# schematics.net
KiCad netlist of a schematic drawn in Altium Designer
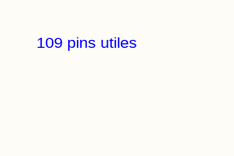
[diagram p0: schematics.schdoc, top left]
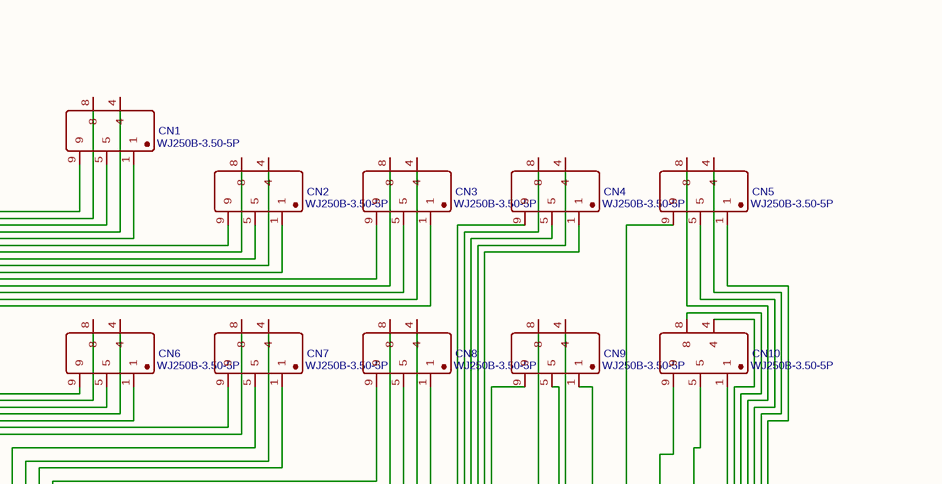
[diagram p1: schematics.schdoc, top right]
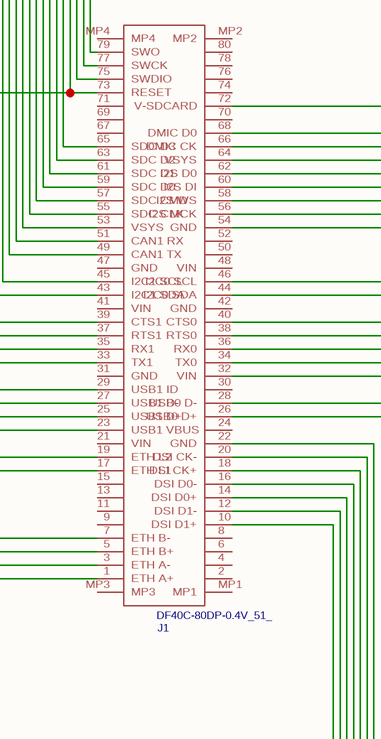
[diagram p2: schematics.schdoc, bottom left]
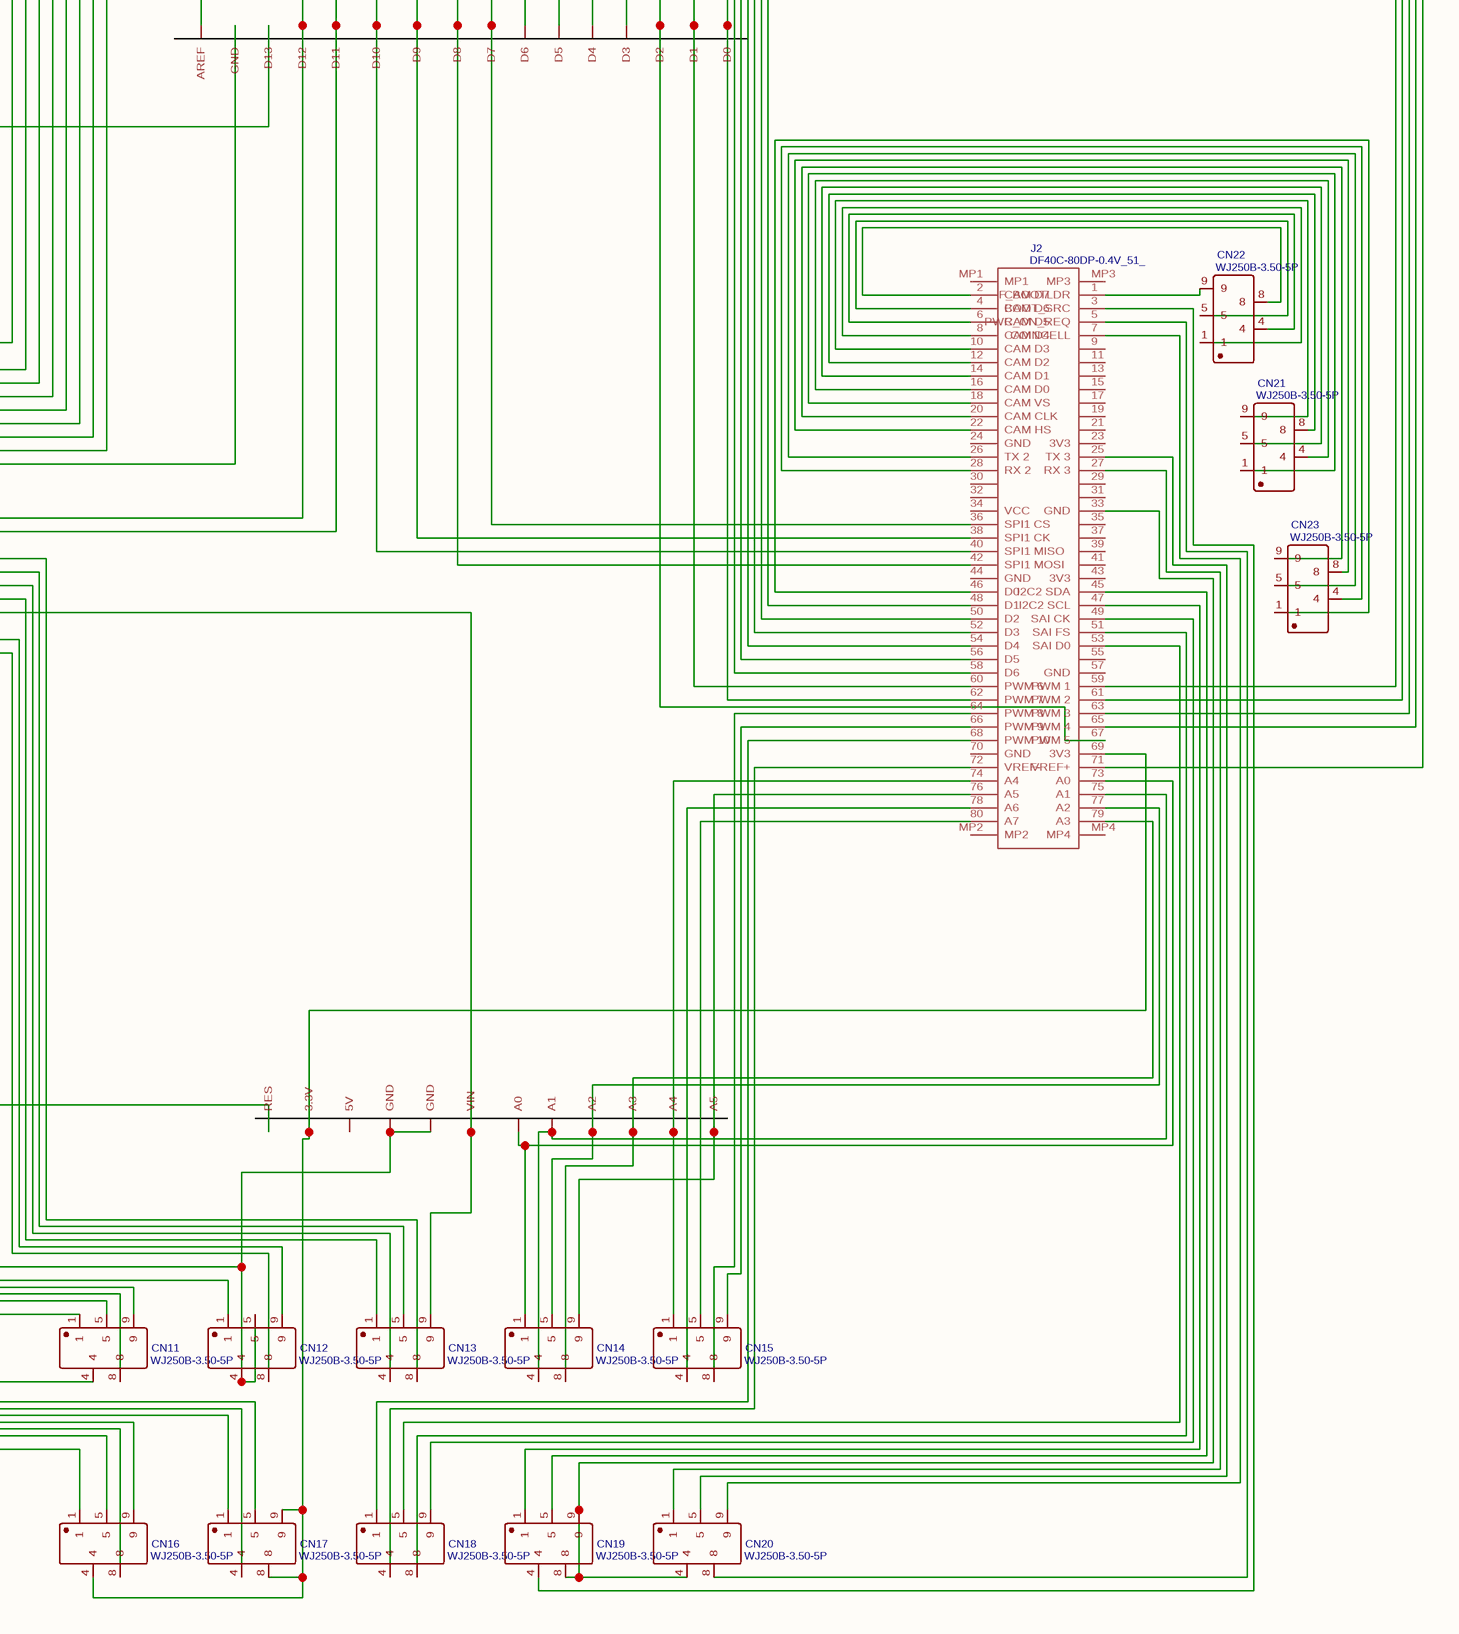
[diagram p3: schematics.schdoc, bottom right]

(export (version "E")
  (design (tool "Eeschema 10.0.6"))
  (components
    (comp (ref "CN1")
      (value "WJ250B-3.50-5P")
      (fields (field (name "BOM_SUPPLIER PART") "C8453"))
      (libsource (lib "altium-import") (part "root_3_WJ250B-3.50-5P_"))
    )
    (comp (ref "CN2")
      (value "WJ250B-3.50-5P")
      (fields (field (name "BOM_SUPPLIER PART") "C8453"))
      (libsource (lib "altium-import") (part "root_3_WJ250B-3.50-5P_"))
    )
    (comp (ref "CN3")
      (value "WJ250B-3.50-5P")
      (fields (field (name "BOM_SUPPLIER PART") "C8453"))
      (libsource (lib "altium-import") (part "root_3_WJ250B-3.50-5P_"))
    )
    (comp (ref "CN4")
      (value "WJ250B-3.50-5P")
      (fields (field (name "BOM_SUPPLIER PART") "C8453"))
      (libsource (lib "altium-import") (part "root_3_WJ250B-3.50-5P_"))
    )
    (comp (ref "CN5")
      (value "WJ250B-3.50-5P")
      (fields (field (name "BOM_SUPPLIER PART") "C8453"))
      (libsource (lib "altium-import") (part "root_3_WJ250B-3.50-5P_"))
    )
    (comp (ref "CN6")
      (value "WJ250B-3.50-5P")
      (fields (field (name "BOM_SUPPLIER PART") "C8453"))
      (libsource (lib "altium-import") (part "root_3_WJ250B-3.50-5P_"))
    )
    (comp (ref "CN7")
      (value "WJ250B-3.50-5P")
      (fields (field (name "BOM_SUPPLIER PART") "C8453"))
      (libsource (lib "altium-import") (part "root_3_WJ250B-3.50-5P_"))
    )
    (comp (ref "CN8")
      (value "WJ250B-3.50-5P")
      (fields (field (name "BOM_SUPPLIER PART") "C8453"))
      (libsource (lib "altium-import") (part "root_3_WJ250B-3.50-5P_"))
    )
    (comp (ref "CN9")
      (value "WJ250B-3.50-5P")
      (fields (field (name "BOM_SUPPLIER PART") "C8453"))
      (libsource (lib "altium-import") (part "root_3_WJ250B-3.50-5P_"))
    )
    (comp (ref "CN10")
      (value "WJ250B-3.50-5P")
      (fields (field (name "BOM_SUPPLIER PART") "C8453"))
      (libsource (lib "altium-import") (part "root_3_WJ250B-3.50-5P_"))
    )
    (comp (ref "CN11")
      (value "WJ250B-3.50-5P")
      (fields (field (name "BOM_SUPPLIER PART") "C8453"))
      (libsource (lib "altium-import") (part "root_1_WJ250B-3.50-5P_"))
    )
    (comp (ref "CN12")
      (value "WJ250B-3.50-5P")
      (fields (field (name "BOM_SUPPLIER PART") "C8453"))
      (libsource (lib "altium-import") (part "root_1_WJ250B-3.50-5P_"))
    )
    (comp (ref "CN13")
      (value "WJ250B-3.50-5P")
      (fields (field (name "BOM_SUPPLIER PART") "C8453"))
      (libsource (lib "altium-import") (part "root_1_WJ250B-3.50-5P_"))
    )
    (comp (ref "CN14")
      (value "WJ250B-3.50-5P")
      (fields (field (name "BOM_SUPPLIER PART") "C8453"))
      (libsource (lib "altium-import") (part "root_1_WJ250B-3.50-5P_"))
    )
    (comp (ref "CN15")
      (value "WJ250B-3.50-5P")
      (fields (field (name "BOM_SUPPLIER PART") "C8453"))
      (libsource (lib "altium-import") (part "root_1_WJ250B-3.50-5P_"))
    )
    (comp (ref "CN16")
      (value "WJ250B-3.50-5P")
      (fields (field (name "BOM_SUPPLIER PART") "C8453"))
      (libsource (lib "altium-import") (part "root_1_WJ250B-3.50-5P_"))
    )
    (comp (ref "CN17")
      (value "WJ250B-3.50-5P")
      (fields (field (name "BOM_SUPPLIER PART") "C8453"))
      (libsource (lib "altium-import") (part "root_1_WJ250B-3.50-5P_"))
    )
    (comp (ref "CN18")
      (value "WJ250B-3.50-5P")
      (fields (field (name "BOM_SUPPLIER PART") "C8453"))
      (libsource (lib "altium-import") (part "root_1_WJ250B-3.50-5P_"))
    )
    (comp (ref "CN19")
      (value "WJ250B-3.50-5P")
      (fields (field (name "BOM_SUPPLIER PART") "C8453"))
      (libsource (lib "altium-import") (part "root_1_WJ250B-3.50-5P_"))
    )
    (comp (ref "CN20")
      (value "WJ250B-3.50-5P")
      (fields (field (name "BOM_SUPPLIER PART") "C8453"))
      (libsource (lib "altium-import") (part "root_1_WJ250B-3.50-5P_"))
    )
    (comp (ref "CN21")
      (value "WJ250B-3.50-5P")
      (fields (field (name "BOM_SUPPLIER PART") "C8453"))
      (libsource (lib "altium-import") (part "root_2_WJ250B-3.50-5P_"))
    )
    (comp (ref "CN22")
      (value "WJ250B-3.50-5P")
      (fields (field (name "BOM_SUPPLIER PART") "C8453"))
      (libsource (lib "altium-import") (part "root_2_WJ250B-3.50-5P_"))
    )
    (comp (ref "CN23")
      (value "WJ250B-3.50-5P")
      (fields (field (name "BOM_SUPPLIER PART") "C8453"))
      (libsource (lib "altium-import") (part "root_2_WJ250B-3.50-5P_"))
    )
    (comp (ref "J1")
      (value "DF40C-80DP-0.4V_51_")
      (libsource (lib "altium-import") (part "root_0_DF40C-80DP-0.4V_51__"))
    )
    (comp (ref "J2")
      (value "DF40C-80DP-0.4V_51_")
      (libsource (lib "altium-import") (part "root_2_DF40C-80DP-0.4V_51__"))
    )
    (comp (ref "U1")
      (value "ARDUINO_SHIELDNO_SILK BIG")
      (description "Arduino shield footprint")
      (fields (field (name "CONTRIBUTOR") "SparkFun"))
      (libsource (lib "altium-import") (part "root_0_ARDUINO_SHIELDNO_SILK BIG_"))
    )
  )
  (nets
    (net (code "1") (name "Net-(CN3-Pad8)") (class "Default")
      (node (ref "CN3") (pin "8") (pinfunction "8_8") (pintype "passive"))
      (node (ref "J1") (pin "53") (pinfunction "VSYS_53") (pintype "passive"))
    )
    (net (code "2") (name "Net-(CN8-Pad9)") (class "Default")
      (node (ref "CN8") (pin "9") (pinfunction "9_9") (pintype "passive"))
      (node (ref "J1") (pin "64") (pinfunction "VSYS_64") (pintype "passive"))
    )
    (net (code "3") (name "Net-(CN12-Pad4)") (class "Default")
      (node (ref "CN12") (pin "4") (pinfunction "4_4") (pintype "passive"))
      (node (ref "CN12") (pin "5") (pinfunction "5_5") (pintype "passive"))
      (node (ref "J1") (pin "22") (pinfunction "GND_22") (pintype "passive"))
      (node (ref "U1") (pin "GND@0") (pinfunction "GND_GND@0") (pintype "passive"))
      (node (ref "U1") (pin "GND@1") (pinfunction "GND_GND@1") (pintype "passive"))
    )
    (net (code "4") (name "Net-(CN13-Pad9)") (class "Default")
      (node (ref "CN13") (pin "9") (pinfunction "9_9") (pintype "passive"))
      (node (ref "J1") (pin "32") (pinfunction "VIN_32") (pintype "passive"))
      (node (ref "U1") (pin "VIN") (pinfunction "VIN_VIN") (pintype "passive"))
    )
    (net (code "5") (name "Net-(CN16-Pad4)") (class "Default")
      (node (ref "CN16") (pin "4") (pinfunction "4_4") (pintype "passive"))
      (node (ref "CN17") (pin "8") (pinfunction "8_8") (pintype "passive"))
      (node (ref "CN17") (pin "9") (pinfunction "9_9") (pintype "passive"))
      (node (ref "J2") (pin "69") (pinfunction "3V3_69") (pintype "passive"))
      (node (ref "U1") (pin "3.3V") (pinfunction "3.3V_3.3V") (pintype "passive"))
    )
    (net (code "6") (name "Net-(CN19-Pad8)") (class "Default")
      (node (ref "CN19") (pin "8") (pinfunction "8_8") (pintype "passive"))
      (node (ref "CN19") (pin "9") (pinfunction "9_9") (pintype "passive"))
      (node (ref "CN20") (pin "4") (pinfunction "4_4") (pintype "passive"))
      (node (ref "J2") (pin "33") (pinfunction "GND_33") (pintype "passive"))
    )
    (net (code "7") (name "Net-(J1-CAN1_RX)") (class "Default")
      (node (ref "CN3") (pin "9") (pinfunction "9_9") (pintype "passive"))
      (node (ref "J1") (pin "51") (pinfunction "CAN1_RX_51") (pintype "passive"))
    )
    (net (code "8") (name "Net-(J1-CAN1_TX)") (class "Default")
      (node (ref "CN2") (pin "1") (pinfunction "1_1") (pintype "passive"))
      (node (ref "J1") (pin "49") (pinfunction "CAN1_TX_49") (pintype "passive"))
    )
    (net (code "9") (name "Net-(J1-CTS0)") (class "Default")
      (node (ref "CN13") (pin "8") (pinfunction "8_8") (pintype "passive"))
      (node (ref "J1") (pin "40") (pinfunction "CTS0_40") (pintype "passive"))
    )
    (net (code "10") (name "Net-(J1-CTS1)") (class "Default")
      (node (ref "CN2") (pin "8") (pinfunction "8_8") (pintype "passive"))
      (node (ref "J1") (pin "39") (pinfunction "CTS1_39") (pintype "passive"))
    )
    (net (code "11") (name "Net-(J1-DMIC_CK)") (class "Default")
      (node (ref "CN7") (pin "1") (pinfunction "1_1") (pintype "passive"))
      (node (ref "J1") (pin "66") (pinfunction "DMIC_CK_66") (pintype "passive"))
    )
    (net (code "12") (name "Net-(J1-DMIC_D0)") (class "Default")
      (node (ref "CN7") (pin "4") (pinfunction "4_4") (pintype "passive"))
      (node (ref "J1") (pin "68") (pinfunction "DMIC_D0_68") (pintype "passive"))
    )
    (net (code "13") (name "Net-(J1-DSI_CK+)") (class "Default")
      (node (ref "CN11") (pin "9") (pinfunction "9_9") (pintype "passive"))
      (node (ref "J1") (pin "18") (pinfunction "DSI_CK+_18") (pintype "passive"))
    )
    (net (code "14") (name "Net-(J1-DSI_CK-)") (class "Default")
      (node (ref "CN12") (pin "1") (pinfunction "1_1") (pintype "passive"))
      (node (ref "J1") (pin "20") (pinfunction "DSI_CK-_20") (pintype "passive"))
    )
    (net (code "15") (name "Net-(J1-DSI_D0+)") (class "Default")
      (node (ref "CN11") (pin "5") (pinfunction "5_5") (pintype "passive"))
      (node (ref "J1") (pin "14") (pinfunction "DSI_D0+_14") (pintype "passive"))
    )
    (net (code "16") (name "Net-(J1-DSI_D0-)") (class "Default")
      (node (ref "CN11") (pin "8") (pinfunction "8_8") (pintype "passive"))
      (node (ref "J1") (pin "16") (pinfunction "DSI_D0-_16") (pintype "passive"))
    )
    (net (code "17") (name "Net-(J1-DSI_D1+)") (class "Default")
      (node (ref "CN11") (pin "4") (pinfunction "4_4") (pintype "passive"))
      (node (ref "J1") (pin "10") (pinfunction "DSI_D1+_10") (pintype "passive"))
    )
    (net (code "18") (name "Net-(J1-DSI_D1-)") (class "Default")
      (node (ref "CN11") (pin "1") (pinfunction "1_1") (pintype "passive"))
      (node (ref "J1") (pin "12") (pinfunction "DSI_D1-_12") (pintype "passive"))
    )
    (net (code "19") (name "Net-(J1-ETH_A+)") (class "Default")
      (node (ref "CN17") (pin "5") (pinfunction "5_5") (pintype "passive"))
      (node (ref "J1") (pin "1") (pinfunction "ETH_A+_1") (pintype "passive"))
    )
    (net (code "20") (name "Net-(J1-ETH_A-)") (class "Default")
      (node (ref "CN17") (pin "4") (pinfunction "4_4") (pintype "passive"))
      (node (ref "J1") (pin "3") (pinfunction "ETH_A-_3") (pintype "passive"))
    )
    (net (code "21") (name "Net-(J1-ETH_B+)") (class "Default")
      (node (ref "CN17") (pin "1") (pinfunction "1_1") (pintype "passive"))
      (node (ref "J1") (pin "5") (pinfunction "ETH_B+_5") (pintype "passive"))
    )
    (net (code "22") (name "Net-(J1-ETH_B-)") (class "Default")
      (node (ref "CN16") (pin "9") (pinfunction "9_9") (pintype "passive"))
      (node (ref "J1") (pin "7") (pinfunction "ETH_B-_7") (pintype "passive"))
    )
    (net (code "23") (name "Net-(J1-ETH_L1)") (class "Default")
      (node (ref "CN16") (pin "8") (pinfunction "8_8") (pintype "passive"))
      (node (ref "J1") (pin "17") (pinfunction "ETH_L1_17") (pintype "passive"))
    )
    (net (code "24") (name "Net-(J1-ETH_L2)") (class "Default")
      (node (ref "CN16") (pin "5") (pinfunction "5_5") (pintype "passive"))
      (node (ref "J1") (pin "19") (pinfunction "ETH_L2_19") (pintype "passive"))
    )
    (net (code "25") (name "Net-(J1-GND-Pad54)") (class "Default")
      (node (ref "J1") (pin "54") (pinfunction "GND_54") (pintype "passive"))
      (node (ref "U1") (pin "GND@2") (pinfunction "GND_GND@2") (pintype "passive"))
    )
    (net (code "26") (name "Net-(J1-I2C0_SCL)") (class "Default")
      (node (ref "CN4") (pin "9") (pinfunction "9_9") (pintype "passive"))
      (node (ref "J1") (pin "46") (pinfunction "I2C0_SCL_46") (pintype "passive"))
      (node (ref "U1") (pin "D12") (pinfunction "D12_D12") (pintype "passive"))
    )
    (net (code "27") (name "Net-(J1-I2C0_SDA)") (class "Default")
      (node (ref "CN4") (pin "8") (pinfunction "8_8") (pintype "passive"))
      (node (ref "J1") (pin "44") (pinfunction "I2C0_SDA_44") (pintype "passive"))
      (node (ref "U1") (pin "D11") (pinfunction "D11_D11") (pintype "passive"))
    )
    (net (code "28") (name "Net-(J1-I2C1_SCL)") (class "Default")
      (node (ref "CN2") (pin "4") (pinfunction "4_4") (pintype "passive"))
      (node (ref "J1") (pin "45") (pinfunction "I2C1_SCL_45") (pintype "passive"))
    )
    (net (code "29") (name "Net-(J1-I2C1_SDA)") (class "Default")
      (node (ref "CN2") (pin "5") (pinfunction "5_5") (pintype "passive"))
      (node (ref "J1") (pin "43") (pinfunction "I2C1_SDA_43") (pintype "passive"))
    )
    (net (code "30") (name "Net-(J1-I2S_D0)") (class "Default")
      (node (ref "CN8") (pin "8") (pinfunction "8_8") (pintype "passive"))
      (node (ref "J1") (pin "62") (pinfunction "I2S_D0_62") (pintype "passive"))
    )
    (net (code "31") (name "Net-(J1-I2S_DI)") (class "Default")
      (node (ref "CN8") (pin "5") (pinfunction "5_5") (pintype "passive"))
      (node (ref "J1") (pin "60") (pinfunction "I2S_DI_60") (pintype "passive"))
    )
    (net (code "32") (name "Net-(J1-I2S_MCK)") (class "Default")
      (node (ref "CN8") (pin "1") (pinfunction "1_1") (pintype "passive"))
      (node (ref "J1") (pin "56") (pinfunction "I2S_MCK_56") (pintype "passive"))
    )
    (net (code "33") (name "Net-(J1-I2S_WS)") (class "Default")
      (node (ref "CN8") (pin "4") (pinfunction "4_4") (pintype "passive"))
      (node (ref "J1") (pin "58") (pinfunction "I2S_WS_58") (pintype "passive"))
    )
    (net (code "34") (name "Net-(J1-RESET)") (class "Default")
      (node (ref "CN6") (pin "4") (pinfunction "4_4") (pintype "passive"))
      (node (ref "J1") (pin "73") (pinfunction "RESET_73") (pintype "passive"))
      (node (ref "U1") (pin "RES") (pinfunction "RES_RES") (pintype "passive"))
    )
    (net (code "35") (name "Net-(J1-RTS0)") (class "Default")
      (node (ref "CN13") (pin "5") (pinfunction "5_5") (pintype "passive"))
      (node (ref "J1") (pin "38") (pinfunction "RTS0_38") (pintype "passive"))
    )
    (net (code "36") (name "Net-(J1-RTS1)") (class "Default")
      (node (ref "CN2") (pin "9") (pinfunction "9_9") (pintype "passive"))
      (node (ref "J1") (pin "37") (pinfunction "RTS1_37") (pintype "passive"))
    )
    (net (code "37") (name "Net-(J1-RX0)") (class "Default")
      (node (ref "CN13") (pin "4") (pinfunction "4_4") (pintype "passive"))
      (node (ref "J1") (pin "36") (pinfunction "RX0_36") (pintype "passive"))
    )
    (net (code "38") (name "Net-(J1-RX1)") (class "Default")
      (node (ref "CN1") (pin "1") (pinfunction "1_1") (pintype "passive"))
      (node (ref "J1") (pin "35") (pinfunction "RX1_35") (pintype "passive"))
      (node (ref "U1") (pin "D13") (pinfunction "D13_D13") (pintype "passive"))
    )
    (net (code "39") (name "Net-(J1-SDC_CLK)") (class "Default")
      (node (ref "CN3") (pin "5") (pinfunction "5_5") (pintype "passive"))
      (node (ref "J1") (pin "55") (pinfunction "SDC_CLK_55") (pintype "passive"))
    )
    (net (code "40") (name "Net-(J1-SDC_CMD)") (class "Default")
      (node (ref "CN3") (pin "4") (pinfunction "4_4") (pintype "passive"))
      (node (ref "J1") (pin "57") (pinfunction "SDC_CMD_57") (pintype "passive"))
    )
    (net (code "41") (name "Net-(J1-SDC_D0)") (class "Default")
      (node (ref "CN3") (pin "1") (pinfunction "1_1") (pintype "passive"))
      (node (ref "J1") (pin "59") (pinfunction "SDC_D0_59") (pintype "passive"))
    )
    (net (code "42") (name "Net-(J1-SDC_D1)") (class "Default")
      (node (ref "CN6") (pin "9") (pinfunction "9_9") (pintype "passive"))
      (node (ref "J1") (pin "61") (pinfunction "SDC_D1_61") (pintype "passive"))
    )
    (net (code "43") (name "Net-(J1-SDC_D2)") (class "Default")
      (node (ref "CN6") (pin "8") (pinfunction "8_8") (pintype "passive"))
      (node (ref "J1") (pin "63") (pinfunction "SDC_D2_63") (pintype "passive"))
    )
    (net (code "44") (name "Net-(J1-SDC_D3)") (class "Default")
      (node (ref "CN6") (pin "5") (pinfunction "5_5") (pintype "passive"))
      (node (ref "J1") (pin "65") (pinfunction "SDC_D3_65") (pintype "passive"))
    )
    (net (code "45") (name "Net-(J1-SWCK)") (class "Default")
      (node (ref "CN7") (pin "9") (pinfunction "9_9") (pintype "passive"))
      (node (ref "J1") (pin "77") (pinfunction "SWCK_77") (pintype "passive"))
    )
    (net (code "46") (name "Net-(J1-SWDIO)") (class "Default")
      (node (ref "CN6") (pin "1") (pinfunction "1_1") (pintype "passive"))
      (node (ref "J1") (pin "75") (pinfunction "SWDIO_75") (pintype "passive"))
    )
    (net (code "47") (name "Net-(J1-SWO)") (class "Default")
      (node (ref "CN7") (pin "8") (pinfunction "8_8") (pintype "passive"))
      (node (ref "J1") (pin "79") (pinfunction "SWO_79") (pintype "passive"))
    )
    (net (code "48") (name "Net-(J1-TX0)") (class "Default")
      (node (ref "CN13") (pin "1") (pinfunction "1_1") (pintype "passive"))
      (node (ref "J1") (pin "34") (pinfunction "TX0_34") (pintype "passive"))
    )
    (net (code "49") (name "Net-(J1-TX1)") (class "Default")
      (node (ref "CN1") (pin "4") (pinfunction "4_4") (pintype "passive"))
      (node (ref "J1") (pin "33") (pinfunction "TX1_33") (pintype "passive"))
    )
    (net (code "50") (name "Net-(J1-USB0_D+)") (class "Default")
      (node (ref "CN12") (pin "8") (pinfunction "8_8") (pintype "passive"))
      (node (ref "J1") (pin "26") (pinfunction "USB0_D+_26") (pintype "passive"))
    )
    (net (code "51") (name "Net-(J1-USB0_D-)") (class "Default")
      (node (ref "CN12") (pin "9") (pinfunction "9_9") (pintype "passive"))
      (node (ref "J1") (pin "28") (pinfunction "USB0_D-_28") (pintype "passive"))
    )
    (net (code "52") (name "Net-(J1-USB1_D+)") (class "Default")
      (node (ref "CN1") (pin "9") (pinfunction "9_9") (pintype "passive"))
      (node (ref "J1") (pin "25") (pinfunction "USB1_D+_25") (pintype "passive"))
    )
    (net (code "53") (name "Net-(J1-USB1_D-)") (class "Default")
      (node (ref "CN1") (pin "8") (pinfunction "8_8") (pintype "passive"))
      (node (ref "J1") (pin "27") (pinfunction "USB1_D-_27") (pintype "passive"))
    )
    (net (code "54") (name "Net-(J1-USB1_ID)") (class "Default")
      (node (ref "CN1") (pin "5") (pinfunction "5_5") (pintype "passive"))
      (node (ref "J1") (pin "29") (pinfunction "USB1_ID_29") (pintype "passive"))
    )
    (net (code "55") (name "Net-(J1-USB1_VBUS)") (class "Default")
      (node (ref "CN16") (pin "1") (pinfunction "1_1") (pintype "passive"))
      (node (ref "J1") (pin "23") (pinfunction "USB1_VBUS_23") (pintype "passive"))
    )
    (net (code "56") (name "Net-(J1-V-SDCARD)") (class "Default")
      (node (ref "CN7") (pin "5") (pinfunction "5_5") (pintype "passive"))
      (node (ref "J1") (pin "72") (pinfunction "V-SDCARD_72") (pintype "passive"))
    )
    (net (code "57") (name "Net-(J2-A0)") (class "Default")
      (node (ref "CN14") (pin "1") (pinfunction "1_1") (pintype "passive"))
      (node (ref "J2") (pin "73") (pinfunction "A0_73") (pintype "passive"))
      (node (ref "U1") (pin "A0") (pinfunction "A0_A0") (pintype "passive"))
    )
    (net (code "58") (name "Net-(J2-A1)") (class "Default")
      (node (ref "CN14") (pin "4") (pinfunction "4_4") (pintype "passive"))
      (node (ref "J2") (pin "75") (pinfunction "A1_75") (pintype "passive"))
      (node (ref "U1") (pin "A1") (pinfunction "A1_A1") (pintype "passive"))
    )
    (net (code "59") (name "Net-(J2-A2)") (class "Default")
      (node (ref "CN14") (pin "5") (pinfunction "5_5") (pintype "passive"))
      (node (ref "J2") (pin "77") (pinfunction "A2_77") (pintype "passive"))
      (node (ref "U1") (pin "A2") (pinfunction "A2_A2") (pintype "passive"))
    )
    (net (code "60") (name "Net-(J2-A3)") (class "Default")
      (node (ref "CN14") (pin "8") (pinfunction "8_8") (pintype "passive"))
      (node (ref "J2") (pin "79") (pinfunction "A3_79") (pintype "passive"))
      (node (ref "U1") (pin "A3") (pinfunction "A3_A3") (pintype "passive"))
    )
    (net (code "61") (name "Net-(J2-A4)") (class "Default")
      (node (ref "CN14") (pin "9") (pinfunction "9_9") (pintype "passive"))
      (node (ref "CN15") (pin "1") (pinfunction "1_1") (pintype "passive"))
      (node (ref "J2") (pin "74") (pinfunction "A4_74") (pintype "passive"))
      (node (ref "J2") (pin "76") (pinfunction "A5_76") (pintype "passive"))
      (node (ref "U1") (pin "A4") (pinfunction "A4_A4") (pintype "passive"))
      (node (ref "U1") (pin "A5") (pinfunction "A5_A5") (pintype "passive"))
    )
    (net (code "62") (name "Net-(J2-A6)") (class "Default")
      (node (ref "CN15") (pin "4") (pinfunction "4_4") (pintype "passive"))
      (node (ref "J2") (pin "78") (pinfunction "A6_78") (pintype "passive"))
    )
    (net (code "63") (name "Net-(J2-A7)") (class "Default")
      (node (ref "CN15") (pin "5") (pinfunction "5_5") (pintype "passive"))
      (node (ref "J2") (pin "80") (pinfunction "A7_80") (pintype "passive"))
    )
    (net (code "64") (name "Net-(J2-BOOT_SRC)") (class "Default")
      (node (ref "CN19") (pin "4") (pinfunction "4_4") (pintype "passive"))
      (node (ref "J2") (pin "3") (pinfunction "BOOT_SRC_3") (pintype "passive"))
    )
    (net (code "65") (name "Net-(J2-CAM_CLK)") (class "Default")
      (node (ref "CN23") (pin "9") (pinfunction "9_9") (pintype "passive"))
      (node (ref "J2") (pin "20") (pinfunction "CAM_CLK_20") (pintype "passive"))
    )
    (net (code "66") (name "Net-(J2-CAM_D0)") (class "Default")
      (node (ref "CN21") (pin "4") (pinfunction "4_4") (pintype "passive"))
      (node (ref "J2") (pin "16") (pinfunction "CAM_D0_16") (pintype "passive"))
    )
    (net (code "67") (name "Net-(J2-CAM_D1)") (class "Default")
      (node (ref "CN21") (pin "5") (pinfunction "5_5") (pintype "passive"))
      (node (ref "J2") (pin "14") (pinfunction "CAM_D1_14") (pintype "passive"))
    )
    (net (code "68") (name "Net-(J2-CAM_D2)") (class "Default")
      (node (ref "CN21") (pin "8") (pinfunction "8_8") (pintype "passive"))
      (node (ref "J2") (pin "12") (pinfunction "CAM_D2_12") (pintype "passive"))
    )
    (net (code "69") (name "Net-(J2-CAM_D3)") (class "Default")
      (node (ref "CN21") (pin "9") (pinfunction "9_9") (pintype "passive"))
      (node (ref "J2") (pin "10") (pinfunction "CAM_D3_10") (pintype "passive"))
    )
    (net (code "70") (name "Net-(J2-CAM_D4)") (class "Default")
      (node (ref "CN22") (pin "1") (pinfunction "1_1") (pintype "passive"))
      (node (ref "J2") (pin "8") (pinfunction "CAM_D4_8") (pintype "passive"))
    )
    (net (code "71") (name "Net-(J2-CAM_D5)") (class "Default")
      (node (ref "CN22") (pin "4") (pinfunction "4_4") (pintype "passive"))
      (node (ref "J2") (pin "6") (pinfunction "CAM_D5_6") (pintype "passive"))
    )
    (net (code "72") (name "Net-(J2-CAM_D6)") (class "Default")
      (node (ref "CN22") (pin "5") (pinfunction "5_5") (pintype "passive"))
      (node (ref "J2") (pin "4") (pinfunction "CAM_D6_4") (pintype "passive"))
    )
    (net (code "73") (name "Net-(J2-CAM_D7)") (class "Default")
      (node (ref "CN22") (pin "8") (pinfunction "8_8") (pintype "passive"))
      (node (ref "J2") (pin "2") (pinfunction "CAM_D7_2") (pintype "passive"))
    )
    (net (code "74") (name "Net-(J2-CAM_HS)") (class "Default")
      (node (ref "CN23") (pin "8") (pinfunction "8_8") (pintype "passive"))
      (node (ref "J2") (pin "22") (pinfunction "CAM_HS_22") (pintype "passive"))
    )
    (net (code "75") (name "Net-(J2-CAM_VS)") (class "Default")
      (node (ref "CN21") (pin "1") (pinfunction "1_1") (pintype "passive"))
      (node (ref "J2") (pin "18") (pinfunction "CAM_VS_18") (pintype "passive"))
    )
    (net (code "76") (name "Net-(J2-COINCELL)") (class "Default")
      (node (ref "CN20") (pin "9") (pinfunction "9_9") (pintype "passive"))
      (node (ref "J2") (pin "7") (pinfunction "COINCELL_7") (pintype "passive"))
    )
    (net (code "77") (name "Net-(J2-D0)") (class "Default")
      (node (ref "CN23") (pin "1") (pinfunction "1_1") (pintype "passive"))
      (node (ref "J2") (pin "46") (pinfunction "D0_46") (pintype "passive"))
    )
    (net (code "78") (name "Net-(J2-D1)") (class "Default")
      (node (ref "CN5") (pin "1") (pinfunction "1_1") (pintype "passive"))
      (node (ref "J2") (pin "48") (pinfunction "D1_48") (pintype "passive"))
    )
    (net (code "79") (name "Net-(J2-D2)") (class "Default")
      (node (ref "CN5") (pin "4") (pinfunction "4_4") (pintype "passive"))
      (node (ref "J2") (pin "50") (pinfunction "D2_50") (pintype "passive"))
    )
    (net (code "80") (name "Net-(J2-D3)") (class "Default")
      (node (ref "CN5") (pin "5") (pinfunction "5_5") (pintype "passive"))
      (node (ref "J2") (pin "52") (pinfunction "D3_52") (pintype "passive"))
    )
    (net (code "81") (name "Net-(J2-D4)") (class "Default")
      (node (ref "CN5") (pin "8") (pinfunction "8_8") (pintype "passive"))
      (node (ref "J2") (pin "54") (pinfunction "D4_54") (pintype "passive"))
    )
    (net (code "82") (name "Net-(J2-D5)") (class "Default")
      (node (ref "CN10") (pin "8") (pinfunction "8_8") (pintype "passive"))
      (node (ref "J2") (pin "56") (pinfunction "D5_56") (pintype "passive"))
    )
    (net (code "83") (name "Net-(J2-D6)") (class "Default")
      (node (ref "CN10") (pin "4") (pinfunction "4_4") (pintype "passive"))
      (node (ref "J2") (pin "58") (pinfunction "D6_58") (pintype "passive"))
    )
    (net (code "84") (name "Net-(J2-F_BOOTLDR)") (class "Default")
      (node (ref "CN22") (pin "9") (pinfunction "9_9") (pintype "passive"))
      (node (ref "J2") (pin "1") (pinfunction "F_BOOTLDR_1") (pintype "passive"))
    )
    (net (code "85") (name "Net-(J2-I2C2_SCL)") (class "Default")
      (node (ref "CN19") (pin "1") (pinfunction "1_1") (pintype "passive"))
      (node (ref "J2") (pin "47") (pinfunction "I2C2_SCL_47") (pintype "passive"))
    )
    (net (code "86") (name "Net-(J2-I2C2_SDA)") (class "Default")
      (node (ref "CN19") (pin "5") (pinfunction "5_5") (pintype "passive"))
      (node (ref "J2") (pin "45") (pinfunction "I2C2_SDA_45") (pintype "passive"))
    )
    (net (code "87") (name "Net-(J2-PWM_1)") (class "Default")
      (node (ref "CN9") (pin "8") (pinfunction "8_8") (pintype "passive"))
      (node (ref "J2") (pin "59") (pinfunction "PWM_1_59") (pintype "passive"))
      (node (ref "U1") (pin "D6") (pinfunction "D6_D6") (pintype "passive"))
    )
    (net (code "88") (name "Net-(J2-PWM_2)") (class "Default")
      (node (ref "CN9") (pin "5") (pinfunction "5_5") (pintype "passive"))
      (node (ref "J2") (pin "61") (pinfunction "PWM_2_61") (pintype "passive"))
      (node (ref "U1") (pin "D5") (pinfunction "D5_D5") (pintype "passive"))
    )
    (net (code "89") (name "Net-(J2-PWM_3)") (class "Default")
      (node (ref "CN9") (pin "1") (pinfunction "1_1") (pintype "passive"))
      (node (ref "J2") (pin "63") (pinfunction "PWM_3_63") (pintype "passive"))
      (node (ref "U1") (pin "D4") (pinfunction "D4_D4") (pintype "passive"))
    )
    (net (code "90") (name "Net-(J2-PWM_4)") (class "Default")
      (node (ref "CN5") (pin "9") (pinfunction "9_9") (pintype "passive"))
      (node (ref "J2") (pin "65") (pinfunction "PWM_4_65") (pintype "passive"))
      (node (ref "U1") (pin "D3") (pinfunction "D3_D3") (pintype "passive"))
    )
    (net (code "91") (name "Net-(J2-PWM_5)") (class "Default")
      (node (ref "CN10") (pin "9") (pinfunction "9_9") (pintype "passive"))
      (node (ref "J2") (pin "67") (pinfunction "PWM_5_67") (pintype "passive"))
      (node (ref "U1") (pin "D2") (pinfunction "D2_D2") (pintype "passive"))
    )
    (net (code "92") (name "Net-(J2-PWM_6)") (class "Default")
      (node (ref "CN10") (pin "5") (pinfunction "5_5") (pintype "passive"))
      (node (ref "J2") (pin "60") (pinfunction "PWM_6_60") (pintype "passive"))
      (node (ref "U1") (pin "TX") (pinfunction "D1_TX") (pintype "passive"))
    )
    (net (code "93") (name "Net-(J2-PWM_7)") (class "Default")
      (node (ref "CN10") (pin "1") (pinfunction "1_1") (pintype "passive"))
      (node (ref "J2") (pin "62") (pinfunction "PWM_7_62") (pintype "passive"))
      (node (ref "U1") (pin "RX") (pinfunction "D0_RX") (pintype "passive"))
    )
    (net (code "94") (name "Net-(J2-PWM_8)") (class "Default")
      (node (ref "CN15") (pin "8") (pinfunction "8_8") (pintype "passive"))
      (node (ref "J2") (pin "64") (pinfunction "PWM_8_64") (pintype "passive"))
    )
    (net (code "95") (name "Net-(J2-PWM_9)") (class "Default")
      (node (ref "CN15") (pin "9") (pinfunction "9_9") (pintype "passive"))
      (node (ref "J2") (pin "66") (pinfunction "PWM_9_66") (pintype "passive"))
    )
    (net (code "96") (name "Net-(J2-PWM_10)") (class "Default")
      (node (ref "CN18") (pin "1") (pinfunction "1_1") (pintype "passive"))
      (node (ref "J2") (pin "68") (pinfunction "PWM_10_68") (pintype "passive"))
    )
    (net (code "97") (name "Net-(J2-PWR_ON_REQ)") (class "Default")
      (node (ref "CN20") (pin "8") (pinfunction "8_8") (pintype "passive"))
      (node (ref "J2") (pin "5") (pinfunction "PWR_ON_REQ_5") (pintype "passive"))
    )
    (net (code "98") (name "Net-(J2-RX_2)") (class "Default")
      (node (ref "CN23") (pin "4") (pinfunction "4_4") (pintype "passive"))
      (node (ref "J2") (pin "28") (pinfunction "RX_2_28") (pintype "passive"))
    )
    (net (code "99") (name "Net-(J2-RX_3)") (class "Default")
      (node (ref "CN20") (pin "1") (pinfunction "1_1") (pintype "passive"))
      (node (ref "J2") (pin "27") (pinfunction "RX_3_27") (pintype "passive"))
    )
    (net (code "100") (name "Net-(J2-SAI_CK)") (class "Default")
      (node (ref "CN18") (pin "9") (pinfunction "9_9") (pintype "passive"))
      (node (ref "J2") (pin "49") (pinfunction "SAI_CK_49") (pintype "passive"))
    )
    (net (code "101") (name "Net-(J2-SAI_D0)") (class "Default")
      (node (ref "CN18") (pin "5") (pinfunction "5_5") (pintype "passive"))
      (node (ref "J2") (pin "53") (pinfunction "SAI_D0_53") (pintype "passive"))
    )
    (net (code "102") (name "Net-(J2-SAI_FS)") (class "Default")
      (node (ref "CN18") (pin "8") (pinfunction "8_8") (pintype "passive"))
      (node (ref "J2") (pin "51") (pinfunction "SAI_FS_51") (pintype "passive"))
    )
    (net (code "103") (name "Net-(J2-SPI1_CK)") (class "Default")
      (node (ref "CN4") (pin "4") (pinfunction "4_4") (pintype "passive"))
      (node (ref "J2") (pin "38") (pinfunction "SPI1_CK_38") (pintype "passive"))
      (node (ref "U1") (pin "D9") (pinfunction "D9_D9") (pintype "passive"))
    )
    (net (code "104") (name "Net-(J2-SPI1_CS)") (class "Default")
      (node (ref "CN9") (pin "9") (pinfunction "9_9") (pintype "passive"))
      (node (ref "J2") (pin "36") (pinfunction "SPI1_CS_36") (pintype "passive"))
      (node (ref "U1") (pin "D7") (pinfunction "D7_D7") (pintype "passive"))
    )
    (net (code "105") (name "Net-(J2-SPI1_MISO)") (class "Default")
      (node (ref "CN4") (pin "5") (pinfunction "5_5") (pintype "passive"))
      (node (ref "J2") (pin "40") (pinfunction "SPI1_MISO_40") (pintype "passive"))
      (node (ref "U1") (pin "D10") (pinfunction "D10_D10") (pintype "passive"))
    )
    (net (code "106") (name "Net-(J2-SPI1_MOSI)") (class "Default")
      (node (ref "CN4") (pin "1") (pinfunction "1_1") (pintype "passive"))
      (node (ref "J2") (pin "42") (pinfunction "SPI1_MOSI_42") (pintype "passive"))
      (node (ref "U1") (pin "D8") (pinfunction "D8_D8") (pintype "passive"))
    )
    (net (code "107") (name "Net-(J2-TX_2)") (class "Default")
      (node (ref "CN23") (pin "5") (pinfunction "5_5") (pintype "passive"))
      (node (ref "J2") (pin "26") (pinfunction "TX_2_26") (pintype "passive"))
    )
    (net (code "108") (name "Net-(J2-TX_3)") (class "Default")
      (node (ref "CN20") (pin "5") (pinfunction "5_5") (pintype "passive"))
      (node (ref "J2") (pin "25") (pinfunction "TX_3_25") (pintype "passive"))
    )
    (net (code "109") (name "Net-(J2-VREF+)") (class "Default")
      (node (ref "CN9") (pin "4") (pinfunction "4_4") (pintype "passive"))
      (node (ref "J2") (pin "71") (pinfunction "VREF+_71") (pintype "passive"))
      (node (ref "U1") (pin "AREF") (pinfunction "AREF_AREF") (pintype "passive"))
    )
    (net (code "110") (name "Net-(J2-VREF-)") (class "Default")
      (node (ref "CN18") (pin "4") (pinfunction "4_4") (pintype "passive"))
      (node (ref "J2") (pin "72") (pinfunction "VREF-_72") (pintype "passive"))
    )
    (net (code "111") (name "unconnected-(J1-GND-Pad31)") (class "Default")
      (node (ref "J1") (pin "31") (pinfunction "GND_31") (pintype "passive"))
    )
    (net (code "112") (name "unconnected-(J1-GND-Pad42)") (class "Default")
      (node (ref "J1") (pin "42") (pinfunction "GND_42") (pintype "passive"))
    )
    (net (code "113") (name "unconnected-(J1-GND-Pad47)") (class "Default")
      (node (ref "J1") (pin "47") (pinfunction "GND_47") (pintype "passive"))
    )
    (net (code "114") (name "unconnected-(J1-Pad2)") (class "Default")
      (node (ref "J1") (pin "2") (pintype "passive"))
    )
    (net (code "115") (name "unconnected-(J1-Pad4)") (class "Default")
      (node (ref "J1") (pin "4") (pintype "passive"))
    )
    (net (code "116") (name "unconnected-(J1-Pad6)") (class "Default")
      (node (ref "J1") (pin "6") (pintype "passive"))
    )
    (net (code "117") (name "unconnected-(J1-Pad8)") (class "Default")
      (node (ref "J1") (pin "8") (pintype "passive"))
    )
    (net (code "118") (name "unconnected-(J1-Pad9)") (class "Default")
      (node (ref "J1") (pin "9") (pintype "passive"))
    )
    (net (code "119") (name "unconnected-(J1-Pad11)") (class "Default")
      (node (ref "J1") (pin "11") (pintype "passive"))
    )
    (net (code "120") (name "unconnected-(J1-Pad13)") (class "Default")
      (node (ref "J1") (pin "13") (pintype "passive"))
    )
    (net (code "121") (name "unconnected-(J1-Pad15)") (class "Default")
      (node (ref "J1") (pin "15") (pintype "passive"))
    )
    (net (code "122") (name "unconnected-(J1-Pad24)") (class "Default")
      (node (ref "J1") (pin "24") (pintype "passive"))
    )
    (net (code "123") (name "unconnected-(J1-Pad30)") (class "Default")
      (node (ref "J1") (pin "30") (pintype "passive"))
    )
    (net (code "124") (name "unconnected-(J1-Pad50)") (class "Default")
      (node (ref "J1") (pin "50") (pintype "passive"))
    )
    (net (code "125") (name "unconnected-(J1-Pad52)") (class "Default")
      (node (ref "J1") (pin "52") (pintype "passive"))
    )
    (net (code "126") (name "unconnected-(J1-Pad67)") (class "Default")
      (node (ref "J1") (pin "67") (pintype "passive"))
    )
    (net (code "127") (name "unconnected-(J1-Pad69)") (class "Default")
      (node (ref "J1") (pin "69") (pintype "passive"))
    )
    (net (code "128") (name "unconnected-(J1-Pad70)") (class "Default")
      (node (ref "J1") (pin "70") (pintype "passive"))
    )
    (net (code "129") (name "unconnected-(J1-Pad71)") (class "Default")
      (node (ref "J1") (pin "71") (pintype "passive"))
    )
    (net (code "130") (name "unconnected-(J1-Pad74)") (class "Default")
      (node (ref "J1") (pin "74") (pintype "passive"))
    )
    (net (code "131") (name "unconnected-(J1-Pad76)") (class "Default")
      (node (ref "J1") (pin "76") (pintype "passive"))
    )
    (net (code "132") (name "unconnected-(J1-Pad78)") (class "Default")
      (node (ref "J1") (pin "78") (pintype "passive"))
    )
    (net (code "133") (name "unconnected-(J1-Pad80)") (class "Default")
      (node (ref "J1") (pin "80") (pintype "passive"))
    )
    (net (code "134") (name "unconnected-(J1-PadMP1)") (class "Default")
      (node (ref "J1") (pin "MP1") (pinfunction "MP1_MP1") (pintype "passive"))
    )
    (net (code "135") (name "unconnected-(J1-PadMP2)") (class "Default")
      (node (ref "J1") (pin "MP2") (pinfunction "MP2_MP2") (pintype "passive"))
    )
    (net (code "136") (name "unconnected-(J1-PadMP3)") (class "Default")
      (node (ref "J1") (pin "MP3") (pinfunction "MP3_MP3") (pintype "passive"))
    )
    (net (code "137") (name "unconnected-(J1-PadMP4)") (class "Default")
      (node (ref "J1") (pin "MP4") (pinfunction "MP4_MP4") (pintype "passive"))
    )
    (net (code "138") (name "unconnected-(J1-VIN-Pad21)") (class "Default")
      (node (ref "J1") (pin "21") (pinfunction "VIN_21") (pintype "passive"))
    )
    (net (code "139") (name "unconnected-(J1-VIN-Pad41)") (class "Default")
      (node (ref "J1") (pin "41") (pinfunction "VIN_41") (pintype "passive"))
    )
    (net (code "140") (name "unconnected-(J1-VIN-Pad48)") (class "Default")
      (node (ref "J1") (pin "48") (pinfunction "VIN_48") (pintype "passive"))
    )
    (net (code "141") (name "unconnected-(J2-3V3-Pad23)") (class "Default")
      (node (ref "J2") (pin "23") (pinfunction "3V3_23") (pintype "passive"))
    )
    (net (code "142") (name "unconnected-(J2-3V3-Pad43)") (class "Default")
      (node (ref "J2") (pin "43") (pinfunction "3V3_43") (pintype "passive"))
    )
    (net (code "143") (name "unconnected-(J2-GND-Pad24)") (class "Default")
      (node (ref "J2") (pin "24") (pinfunction "GND_24") (pintype "passive"))
    )
    (net (code "144") (name "unconnected-(J2-GND-Pad44)") (class "Default")
      (node (ref "J2") (pin "44") (pinfunction "GND_44") (pintype "passive"))
    )
    (net (code "145") (name "unconnected-(J2-GND-Pad57)") (class "Default")
      (node (ref "J2") (pin "57") (pinfunction "GND_57") (pintype "passive"))
    )
    (net (code "146") (name "unconnected-(J2-GND-Pad70)") (class "Default")
      (node (ref "J2") (pin "70") (pinfunction "GND_70") (pintype "passive"))
    )
    (net (code "147") (name "unconnected-(J2-Pad9)") (class "Default")
      (node (ref "J2") (pin "9") (pintype "passive"))
    )
    (net (code "148") (name "unconnected-(J2-Pad11)") (class "Default")
      (node (ref "J2") (pin "11") (pintype "passive"))
    )
    (net (code "149") (name "unconnected-(J2-Pad13)") (class "Default")
      (node (ref "J2") (pin "13") (pintype "passive"))
    )
    (net (code "150") (name "unconnected-(J2-Pad15)") (class "Default")
      (node (ref "J2") (pin "15") (pintype "passive"))
    )
    (net (code "151") (name "unconnected-(J2-Pad17)") (class "Default")
      (node (ref "J2") (pin "17") (pintype "passive"))
    )
    (net (code "152") (name "unconnected-(J2-Pad19)") (class "Default")
      (node (ref "J2") (pin "19") (pintype "passive"))
    )
    (net (code "153") (name "unconnected-(J2-Pad21)") (class "Default")
      (node (ref "J2") (pin "21") (pintype "passive"))
    )
    (net (code "154") (name "unconnected-(J2-Pad29)") (class "Default")
      (node (ref "J2") (pin "29") (pintype "passive"))
    )
    (net (code "155") (name "unconnected-(J2-Pad30)") (class "Default")
      (node (ref "J2") (pin "30") (pintype "passive"))
    )
    (net (code "156") (name "unconnected-(J2-Pad31)") (class "Default")
      (node (ref "J2") (pin "31") (pintype "passive"))
    )
    (net (code "157") (name "unconnected-(J2-Pad32)") (class "Default")
      (node (ref "J2") (pin "32") (pintype "passive"))
    )
    (net (code "158") (name "unconnected-(J2-Pad35)") (class "Default")
      (node (ref "J2") (pin "35") (pintype "passive"))
    )
    (net (code "159") (name "unconnected-(J2-Pad37)") (class "Default")
      (node (ref "J2") (pin "37") (pintype "passive"))
    )
    (net (code "160") (name "unconnected-(J2-Pad39)") (class "Default")
      (node (ref "J2") (pin "39") (pintype "passive"))
    )
    (net (code "161") (name "unconnected-(J2-Pad41)") (class "Default")
      (node (ref "J2") (pin "41") (pintype "passive"))
    )
    (net (code "162") (name "unconnected-(J2-Pad55)") (class "Default")
      (node (ref "J2") (pin "55") (pintype "passive"))
    )
    (net (code "163") (name "unconnected-(J2-PadMP1)") (class "Default")
      (node (ref "J2") (pin "MP1") (pinfunction "MP1_MP1") (pintype "passive"))
    )
    (net (code "164") (name "unconnected-(J2-PadMP2)") (class "Default")
      (node (ref "J2") (pin "MP2") (pinfunction "MP2_MP2") (pintype "passive"))
    )
    (net (code "165") (name "unconnected-(J2-PadMP3)") (class "Default")
      (node (ref "J2") (pin "MP3") (pinfunction "MP3_MP3") (pintype "passive"))
    )
    (net (code "166") (name "unconnected-(J2-PadMP4)") (class "Default")
      (node (ref "J2") (pin "MP4") (pinfunction "MP4_MP4") (pintype "passive"))
    )
    (net (code "167") (name "unconnected-(J2-VCC-Pad34)") (class "Default")
      (node (ref "J2") (pin "34") (pinfunction "VCC_34") (pintype "passive"))
    )
    (net (code "168") (name "unconnected-(U1-Pad5V)") (class "Default")
      (node (ref "U1") (pin "5V") (pinfunction "5V_5V") (pintype "passive"))
    )
  )
)
